# TOP.net
KiCad netlist of a schematic drawn in Altium Designer
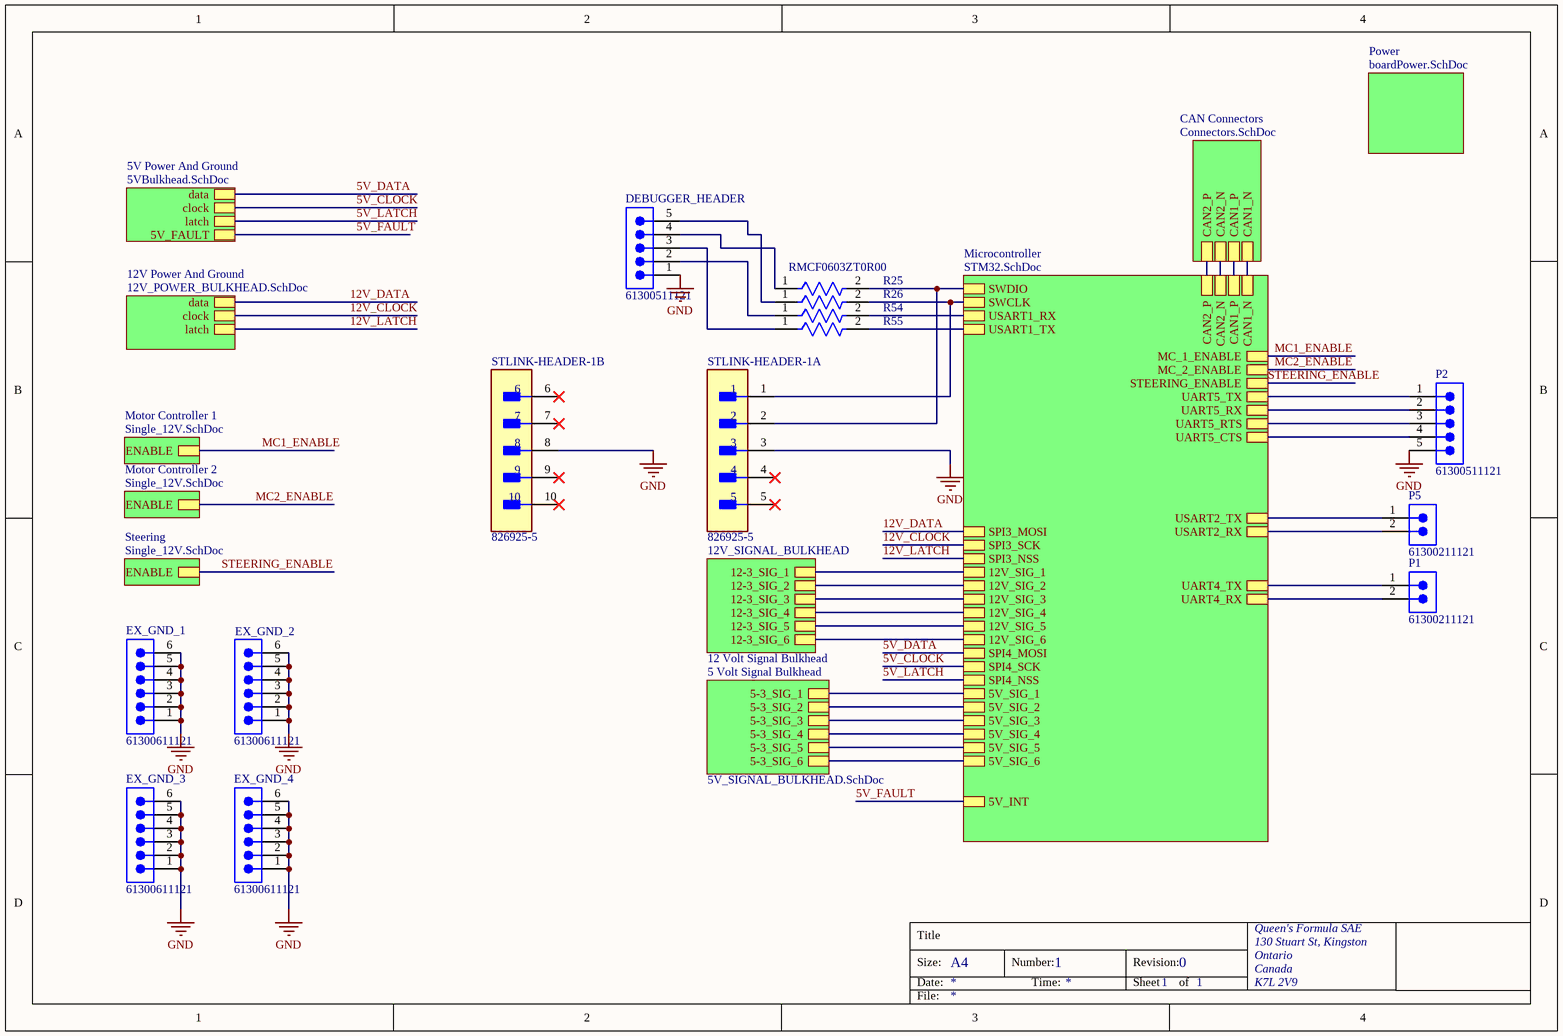
[diagram p0: TOP.SchDoc]

(export (version "E")
  (design (tool "Eeschema 10.0.6"))
  (components
    (comp (ref "DEBUGGER_HEADER")
      (value "61300511121")
      (footprint "61300511121")
      (libsource (lib "Altium Content Vault") (part "Header_Male_1R_05P"))
    )
    (comp (ref "EX_GND_1")
      (value "61300611121")
      (footprint "61300611121")
      (libsource (lib "Altium Content Vault") (part "Header_Male_1R_06P"))
    )
    (comp (ref "EX_GND_2")
      (value "61300611121")
      (footprint "61300611121")
      (libsource (lib "Altium Content Vault") (part "Header_Male_1R_06P"))
    )
    (comp (ref "EX_GND_3")
      (value "61300611121")
      (footprint "61300611121")
      (libsource (lib "Altium Content Vault") (part "Header_Male_1R_06P"))
    )
    (comp (ref "EX_GND_4")
      (value "61300611121")
      (footprint "61300611121")
      (libsource (lib "Altium Content Vault") (part "Header_Male_1R_06P"))
    )
    (comp (ref "P1")
      (value "61300211121")
      (footprint "61300211121")
      (libsource (lib "Altium Content Vault") (part "Header_Male_1R_02P"))
    )
    (comp (ref "P2")
      (value "61300511121")
      (footprint "61300511121")
      (libsource (lib "Altium Content Vault") (part "Header_Male_1R_05P"))
    )
    (comp (ref "P5")
      (value "61300211121")
      (footprint "61300211121")
      (libsource (lib "Altium Content Vault") (part "Header_Male_1R_02P"))
    )
    (comp (ref "R25")
      (value "RMCF0603ZT0R00")
      (footprint "FP-RMCF0603-MFG")
      (description "RES 0 OHM JUMPER 1/10W 0603")
      (fields
        (field (name "OCTOPART") "https://octopart.com/rmcf0603zt0r00-stackpole+electronics-19213618")
        (field (name "MANUFACTURER") "Stackpole")
      )
      (libsource (lib "Altium Content Vault") (part "1029c3af85768c4190bb7ad29bc67b5"))
    )
    (comp (ref "R26")
      (value "RMCF0603ZT0R00")
      (footprint "FP-RMCF0603-MFG")
      (description "RES 0 OHM JUMPER 1/10W 0603")
      (fields
        (field (name "OCTOPART") "https://octopart.com/rmcf0603zt0r00-stackpole+electronics-19213618")
        (field (name "MANUFACTURER") "Stackpole")
      )
      (libsource (lib "Altium Content Vault") (part "1029c3af85768c4190bb7ad29bc67b5"))
    )
    (comp (ref "R54")
      (value "RMCF0603ZT0R00")
      (footprint "FP-RMCF0603-MFG")
      (description "RES 0 OHM JUMPER 1/10W 0603")
      (fields
        (field (name "OCTOPART") "https://octopart.com/rmcf0603zt0r00-stackpole+electronics-19213618")
        (field (name "MANUFACTURER") "Stackpole")
      )
      (libsource (lib "Altium Content Vault") (part "1029c3af85768c4190bb7ad29bc67b5"))
    )
    (comp (ref "R55")
      (value "RMCF0603ZT0R00")
      (footprint "FP-RMCF0603-MFG")
      (description "RES 0 OHM JUMPER 1/10W 0603")
      (fields
        (field (name "OCTOPART") "https://octopart.com/rmcf0603zt0r00-stackpole+electronics-19213618")
        (field (name "MANUFACTURER") "Stackpole")
      )
      (libsource (lib "Altium Content Vault") (part "1029c3af85768c4190bb7ad29bc67b5"))
    )
    (comp (ref "STLINK-HEADER-1")
      (value "826925-5")
      (footprint "FP-826925-5-MFG")
      (description "CONN HEADER VERT 10POS 2.54MM")
      (fields
        (field (name "OCTOPART") "https://octopart.com/826925-5-te+connectivity-41836231")
        (field (name "MANUFACTURER") "TE Connectivity")
      )
      (libsource (lib "Altium Content Vault") (part "de255ff815dec4fe6d5caee7def00c9"))
    )
  )
  (nets
    (net (code "27") (name "/SWCLK") (class "Default")
      (node (ref "R26") (pin "2") (pinfunction "2_2") (pintype "passive"))
      (node (ref "STLINK-HEADER-1") (pin "1") (pinfunction "1_1") (pintype "passive"))
    )
    (net (code "28") (name "/SWDIO") (class "Default")
      (node (ref "R25") (pin "2") (pinfunction "2_2") (pintype "passive"))
      (node (ref "STLINK-HEADER-1") (pin "2") (pinfunction "2_2") (pintype "passive"))
    )
    (net (code "29") (name "/UART4_RX") (class "Default")
      (node (ref "P1") (pin "2") (pinfunction "2_2") (pintype "passive"))
    )
    (net (code "30") (name "/UART4_TX") (class "Default")
      (node (ref "P1") (pin "1") (pinfunction "1_1") (pintype "passive"))
    )
    (net (code "31") (name "/UART5_CTS") (class "Default")
      (node (ref "P2") (pin "4") (pinfunction "4_4") (pintype "passive"))
    )
    (net (code "32") (name "/UART5_RTS") (class "Default")
      (node (ref "P2") (pin "3") (pinfunction "3_3") (pintype "passive"))
    )
    (net (code "33") (name "/UART5_RX") (class "Default")
      (node (ref "P2") (pin "2") (pinfunction "2_2") (pintype "passive"))
    )
    (net (code "34") (name "/UART5_TX") (class "Default")
      (node (ref "P2") (pin "1") (pinfunction "1_1") (pintype "passive"))
    )
    (net (code "35") (name "/USART1_RX") (class "Default")
      (node (ref "R54") (pin "2") (pinfunction "2_2") (pintype "passive"))
    )
    (net (code "36") (name "/USART1_TX") (class "Default")
      (node (ref "R55") (pin "2") (pinfunction "2_2") (pintype "passive"))
    )
    (net (code "37") (name "/USART2_RX") (class "Default")
      (node (ref "P5") (pin "2") (pinfunction "2_2") (pintype "passive"))
    )
    (net (code "38") (name "/USART2_TX") (class "Default")
      (node (ref "P5") (pin "1") (pinfunction "1_1") (pintype "passive"))
    )
    (net (code "39") (name "GND") (class "Default")
      (node (ref "DEBUGGER_HEADER") (pin "1") (pinfunction "1_1") (pintype "passive"))
      (node (ref "EX_GND_1") (pin "1") (pinfunction "1_1") (pintype "passive"))
      (node (ref "EX_GND_1") (pin "2") (pinfunction "2_2") (pintype "passive"))
      (node (ref "EX_GND_1") (pin "3") (pinfunction "3_3") (pintype "passive"))
      (node (ref "EX_GND_1") (pin "4") (pinfunction "4_4") (pintype "passive"))
      (node (ref "EX_GND_1") (pin "5") (pinfunction "5_5") (pintype "passive"))
      (node (ref "EX_GND_1") (pin "6") (pinfunction "6_6") (pintype "passive"))
      (node (ref "EX_GND_2") (pin "1") (pinfunction "1_1") (pintype "passive"))
      (node (ref "EX_GND_2") (pin "2") (pinfunction "2_2") (pintype "passive"))
      (node (ref "EX_GND_2") (pin "3") (pinfunction "3_3") (pintype "passive"))
      (node (ref "EX_GND_2") (pin "4") (pinfunction "4_4") (pintype "passive"))
      (node (ref "EX_GND_2") (pin "5") (pinfunction "5_5") (pintype "passive"))
      (node (ref "EX_GND_2") (pin "6") (pinfunction "6_6") (pintype "passive"))
      (node (ref "EX_GND_3") (pin "1") (pinfunction "1_1") (pintype "passive"))
      (node (ref "EX_GND_3") (pin "2") (pinfunction "2_2") (pintype "passive"))
      (node (ref "EX_GND_3") (pin "3") (pinfunction "3_3") (pintype "passive"))
      (node (ref "EX_GND_3") (pin "4") (pinfunction "4_4") (pintype "passive"))
      (node (ref "EX_GND_3") (pin "5") (pinfunction "5_5") (pintype "passive"))
      (node (ref "EX_GND_3") (pin "6") (pinfunction "6_6") (pintype "passive"))
      (node (ref "EX_GND_4") (pin "1") (pinfunction "1_1") (pintype "passive"))
      (node (ref "EX_GND_4") (pin "2") (pinfunction "2_2") (pintype "passive"))
      (node (ref "EX_GND_4") (pin "3") (pinfunction "3_3") (pintype "passive"))
      (node (ref "EX_GND_4") (pin "4") (pinfunction "4_4") (pintype "passive"))
      (node (ref "EX_GND_4") (pin "5") (pinfunction "5_5") (pintype "passive"))
      (node (ref "EX_GND_4") (pin "6") (pinfunction "6_6") (pintype "passive"))
      (node (ref "P2") (pin "5") (pinfunction "5_5") (pintype "passive"))
      (node (ref "STLINK-HEADER-1") (pin "3") (pinfunction "3_3") (pintype "passive"))
      (node (ref "STLINK-HEADER-1") (pin "8") (pinfunction "8_8") (pintype "passive"))
    )
    (net (code "40") (name "Net-(DEBUGGER_HEADER-Pad2)") (class "Default")
      (node (ref "DEBUGGER_HEADER") (pin "2") (pinfunction "2_2") (pintype "passive"))
      (node (ref "R54") (pin "1") (pinfunction "1_1") (pintype "passive"))
    )
    (net (code "41") (name "Net-(DEBUGGER_HEADER-Pad3)") (class "Default")
      (node (ref "DEBUGGER_HEADER") (pin "3") (pinfunction "3_3") (pintype "passive"))
      (node (ref "R55") (pin "1") (pinfunction "1_1") (pintype "passive"))
    )
    (net (code "42") (name "Net-(DEBUGGER_HEADER-Pad4)") (class "Default")
      (node (ref "DEBUGGER_HEADER") (pin "4") (pinfunction "4_4") (pintype "passive"))
      (node (ref "R25") (pin "1") (pinfunction "1_1") (pintype "passive"))
    )
    (net (code "43") (name "Net-(DEBUGGER_HEADER-Pad5)") (class "Default")
      (node (ref "DEBUGGER_HEADER") (pin "5") (pinfunction "5_5") (pintype "passive"))
      (node (ref "R26") (pin "1") (pinfunction "1_1") (pintype "passive"))
    )
    (net (code "44") (name "unconnected-(STLINK-HEADER-1-Pad4)") (class "Default")
      (node (ref "STLINK-HEADER-1") (pin "4") (pinfunction "4_4") (pintype "passive+no_connect"))
    )
    (net (code "45") (name "unconnected-(STLINK-HEADER-1-Pad5)") (class "Default")
      (node (ref "STLINK-HEADER-1") (pin "5") (pinfunction "5_5") (pintype "passive+no_connect"))
    )
    (net (code "46") (name "unconnected-(STLINK-HEADER-1-Pad6)") (class "Default")
      (node (ref "STLINK-HEADER-1") (pin "6") (pinfunction "6_6") (pintype "passive+no_connect"))
    )
    (net (code "47") (name "unconnected-(STLINK-HEADER-1-Pad7)") (class "Default")
      (node (ref "STLINK-HEADER-1") (pin "7") (pinfunction "7_7") (pintype "passive+no_connect"))
    )
    (net (code "48") (name "unconnected-(STLINK-HEADER-1-Pad9)") (class "Default")
      (node (ref "STLINK-HEADER-1") (pin "9") (pinfunction "9_9") (pintype "passive+no_connect"))
    )
    (net (code "49") (name "unconnected-(STLINK-HEADER-1-Pad10)") (class "Default")
      (node (ref "STLINK-HEADER-1") (pin "10") (pinfunction "10_10") (pintype "passive+no_connect"))
    )
  )
)
